# sensor.net
KiCad netlist of a schematic drawn in Altium Designer
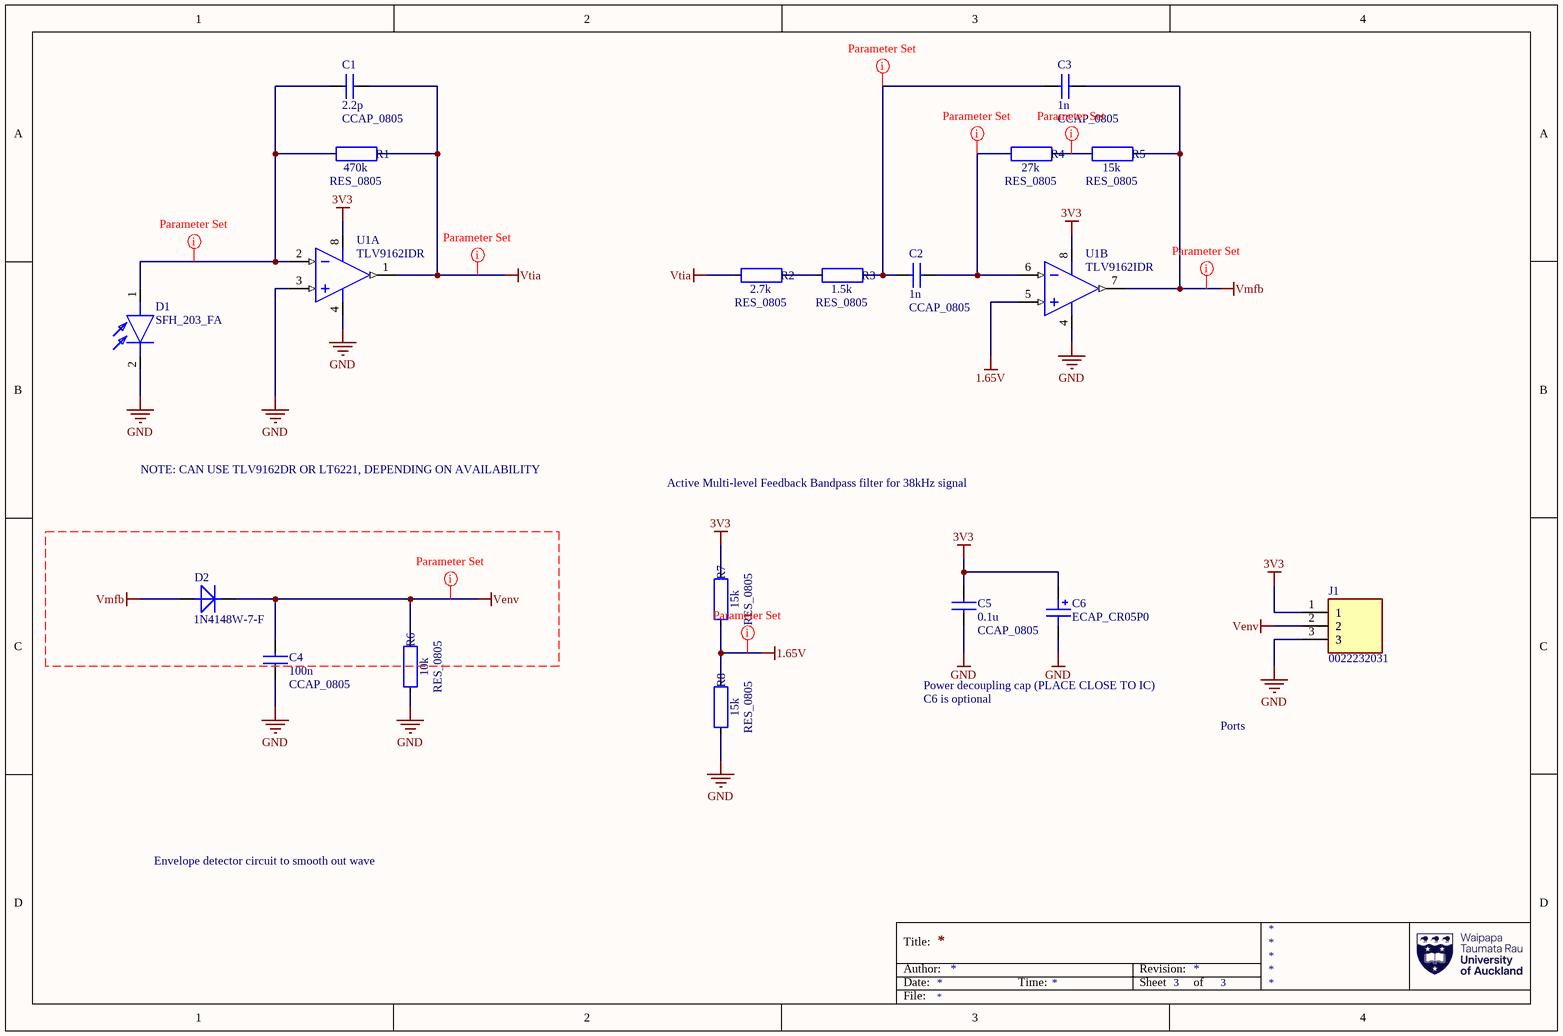
[diagram p0: sensor.SchDoc]

(export (version "E")
  (design (tool "Eeschema 10.0.6"))
  (components
    (comp (ref "C1")
      (value "CCAP_0805")
      (footprint "C0805")
      (description "Generic 0805 cramic capacitor")
      (fields (field (name "ALTIUM_VALUE") "2.2p"))
      (libsource (lib "UGs@UoA") (part "CCAP0805"))
    )
    (comp (ref "C2")
      (value "CCAP_0805")
      (footprint "C0805")
      (description "Generic 0805 cramic capacitor")
      (fields (field (name "ALTIUM_VALUE") "1n"))
      (libsource (lib "UGs@UoA") (part "CCAP0805"))
    )
    (comp (ref "C3")
      (value "CCAP_0805")
      (footprint "C0805")
      (description "Generic 0805 cramic capacitor")
      (fields (field (name "ALTIUM_VALUE") "1n"))
      (libsource (lib "UGs@UoA") (part "CCAP0805"))
    )
    (comp (ref "C4")
      (value "CCAP_0805")
      (footprint "C0805")
      (description "Generic 0805 cramic capacitor")
      (fields (field (name "ALTIUM_VALUE") "100n"))
      (libsource (lib "UGs@UoA") (part "CCAP0805"))
    )
    (comp (ref "C5")
      (value "CCAP_0805")
      (footprint "C0805")
      (description "Generic 0805 cramic capacitor")
      (fields (field (name "ALTIUM_VALUE") "0.1u"))
      (libsource (lib "UGs@UoA") (part "CCAP0805"))
    )
    (comp (ref "C6")
      (value "ECAP_CR05P0")
      (footprint "EC_CR05")
      (description "Generic 5mm pitch TH radial electrolytic capacitor")
      (libsource (lib "UGs@UoA") (part "ECAP"))
    )
    (comp (ref "D1")
      (value "SFH_203_FA")
      (footprint "SamacSys:SFH203FA")
      (description "LED")
      (fields
        (field (name "MANUFACTURER_PART_NUMBER") "SFH 203 FA")
        (field (name "MOUSER PART NUMBER") "720-SFH203FA")
      )
      (libsource (lib "SamacSys") (part "SFH_203_FA"))
    )
    (comp (ref "D2")
      (value "1N4148W-7-F")
      (footprint "SOD123")
      (description "Small Signal Diode, Single, 100 V, 300 mA, 4ns, SOD-123")
      (libsource (lib "UGs@UoA") (part "Diode"))
    )
    (comp (ref "J1")
      (value "0022232031")
      (footprint "HDRV3W87P0X254_1X3_747X635X1105P")
      (description "Connector")
      (libsource (lib "SamacSys") (part "0022232031"))
    )
    (comp (ref "R1")
      (value "RES_0805")
      (footprint "R0805")
      (description "Generic 0805 resistor")
      (fields (field (name "ALTIUM_VALUE") "470k"))
      (libsource (lib "UGs@UoA") (part "RES0805"))
    )
    (comp (ref "R2")
      (value "RES_0805")
      (footprint "R0805")
      (description "Generic 0805 resistor")
      (fields (field (name "ALTIUM_VALUE") "2.7k"))
      (libsource (lib "UGs@UoA") (part "RES0805"))
    )
    (comp (ref "R3")
      (value "RES_0805")
      (footprint "R0805")
      (description "Generic 0805 resistor")
      (fields (field (name "ALTIUM_VALUE") "1.5k"))
      (libsource (lib "UGs@UoA") (part "RES0805"))
    )
    (comp (ref "R4")
      (value "RES_0805")
      (footprint "R0805")
      (description "Generic 0805 resistor")
      (fields (field (name "ALTIUM_VALUE") "27k"))
      (libsource (lib "UGs@UoA") (part "RES0805"))
    )
    (comp (ref "R5")
      (value "RES_0805")
      (footprint "R0805")
      (description "Generic 0805 resistor")
      (fields (field (name "ALTIUM_VALUE") "15k"))
      (libsource (lib "UGs@UoA") (part "RES0805"))
    )
    (comp (ref "R6")
      (value "RES_0805")
      (footprint "R0805")
      (description "Generic 0805 resistor")
      (fields (field (name "ALTIUM_VALUE") "10k"))
      (libsource (lib "") (part "RES0805_1"))
    )
    (comp (ref "R7")
      (value "RES_0805")
      (footprint "R0805")
      (description "Generic 0805 resistor")
      (fields (field (name "ALTIUM_VALUE") "15k"))
      (libsource (lib "") (part "RES0805_1"))
    )
    (comp (ref "R8")
      (value "RES_0805")
      (footprint "R0805")
      (description "Generic 0805 resistor")
      (fields (field (name "ALTIUM_VALUE") "15k"))
      (libsource (lib "") (part "RES0805_1"))
    )
    (comp (ref "U1")
      (value "TLV9162IDR")
      (footprint "SOIC8-Ti-Footprint")
      (description "Dual 10pA 33V/us 11MHz SOIC-8 Operational Amplifier ROHS")
      (libsource (lib "UGs@UoA") (part "DualOpAmp"))
    )
  )
  (nets
    (net (code "1") (name "1.65V") (class "Default")
      (node (ref "R7") (pin "1") (pinfunction "1_1") (pintype "passive"))
      (node (ref "R8") (pin "2") (pinfunction "2_2") (pintype "passive"))
      (node (ref "U1") (pin "5") (pinfunction "2IN+_5") (pintype "input"))
    )
    (net (code "2") (name "3V3") (class "Default")
      (node (ref "C5") (pin "2") (pinfunction "2_2") (pintype "passive"))
      (node (ref "C6") (pin "1") (pinfunction "1_1") (pintype "passive"))
      (node (ref "J1") (pin "1") (pinfunction "1_1") (pintype "passive"))
      (node (ref "R7") (pin "2") (pinfunction "2_2") (pintype "passive"))
      (node (ref "U1") (pin "8") (pinfunction "VCC_8") (pintype "power_in"))
    )
    (net (code "3") (name "GND") (class "Default")
      (node (ref "C4") (pin "2") (pinfunction "2_2") (pintype "passive"))
      (node (ref "C5") (pin "1") (pinfunction "1_1") (pintype "passive"))
      (node (ref "C6") (pin "2") (pinfunction "2_2") (pintype "passive"))
      (node (ref "D1") (pin "2") (pinfunction "K_2") (pintype "passive"))
      (node (ref "J1") (pin "3") (pinfunction "3_3") (pintype "passive"))
      (node (ref "R6") (pin "1") (pinfunction "1_1") (pintype "passive"))
      (node (ref "R8") (pin "1") (pinfunction "1_1") (pintype "passive"))
      (node (ref "U1") (pin "3") (pinfunction "1IN+_3") (pintype "input"))
      (node (ref "U1") (pin "4") (pinfunction "GND_4") (pintype "power_in"))
    )
    (net (code "4") (name "Net-(C2-Pad2)") (class "Default")
      (node (ref "C2") (pin "2") (pinfunction "2_2") (pintype "passive"))
      (node (ref "C3") (pin "2") (pinfunction "2_2") (pintype "passive"))
      (node (ref "R3") (pin "2") (pinfunction "2_2") (pintype "passive"))
    )
    (net (code "5") (name "Net-(D1-A)") (class "Default")
      (node (ref "C1") (pin "2") (pinfunction "2_2") (pintype "passive"))
      (node (ref "D1") (pin "1") (pinfunction "A_1") (pintype "passive"))
      (node (ref "R1") (pin "1") (pinfunction "1_1") (pintype "passive"))
      (node (ref "U1") (pin "2") (pinfunction "1IN-_2") (pintype "input"))
    )
    (net (code "6") (name "Net-(R2-Pad2)") (class "Default")
      (node (ref "R2") (pin "2") (pinfunction "2_2") (pintype "passive"))
      (node (ref "R3") (pin "1") (pinfunction "1_1") (pintype "passive"))
    )
    (net (code "7") (name "Net-(R4-Pad2)") (class "Default")
      (node (ref "R4") (pin "2") (pinfunction "2_2") (pintype "passive"))
      (node (ref "R5") (pin "1") (pinfunction "1_1") (pintype "passive"))
    )
    (net (code "8") (name "Net-(U1B-2IN-)") (class "Default")
      (node (ref "C2") (pin "1") (pinfunction "1_1") (pintype "passive"))
      (node (ref "R4") (pin "1") (pinfunction "1_1") (pintype "passive"))
      (node (ref "U1") (pin "6") (pinfunction "2IN-_6") (pintype "input"))
    )
    (net (code "9") (name "Venv") (class "Default")
      (node (ref "C4") (pin "1") (pinfunction "1_1") (pintype "passive"))
      (node (ref "D2") (pin "1") (pinfunction "K_1") (pintype "passive"))
      (node (ref "J1") (pin "2") (pinfunction "2_2") (pintype "passive"))
      (node (ref "R6") (pin "2") (pinfunction "2_2") (pintype "passive"))
    )
    (net (code "10") (name "Vmfb") (class "Default")
      (node (ref "C3") (pin "1") (pinfunction "1_1") (pintype "passive"))
      (node (ref "D2") (pin "2") (pinfunction "A_2") (pintype "passive"))
      (node (ref "R5") (pin "2") (pinfunction "2_2") (pintype "passive"))
      (node (ref "U1") (pin "7") (pinfunction "2OUT_7") (pintype "output"))
    )
    (net (code "11") (name "Vtia") (class "Default")
      (node (ref "C1") (pin "1") (pinfunction "1_1") (pintype "passive"))
      (node (ref "R1") (pin "2") (pinfunction "2_2") (pintype "passive"))
      (node (ref "R2") (pin "1") (pinfunction "1_1") (pintype "passive"))
      (node (ref "U1") (pin "1") (pinfunction "1OUT_1") (pintype "output"))
    )
  )
)
